# Sheet2.net
KiCad netlist of a schematic drawn in Altium Designer
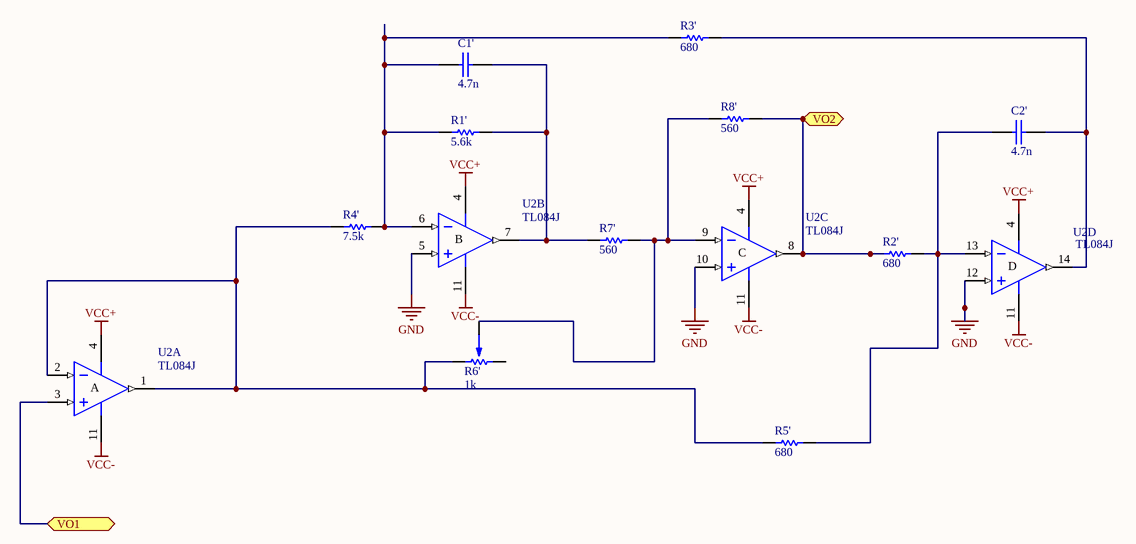
[diagram p0: Sheet2.SchDoc]

(export (version "E")
  (design (tool "Eeschema 10.0.6"))
  (components
    (comp (ref "C1'") (value "4.7n") (footprint "CAP100") (libsource (lib "LIBEBAL") (part "CAP")))
    (comp (ref "C2'") (value "4.7n") (footprint "CAP100") (libsource (lib "LIBEBAL") (part "CAP")))
    (comp (ref "R1'") (value "5.6k") (footprint "0805") (libsource (lib "LIBEBAL") (part "RES")))
    (comp (ref "R2'") (value "680") (footprint "0805") (libsource (lib "LIBEBAL") (part "RES")))
    (comp (ref "R3'") (value "680") (footprint "0805") (libsource (lib "LIBEBAL") (part "RES")))
    (comp (ref "R4'") (value "7.5k") (footprint "0805") (libsource (lib "LIBEBAL") (part "RES")))
    (comp (ref "R5'") (value "680") (footprint "0805") (libsource (lib "LIBEBAL") (part "RES")))
    (comp (ref "R6'") (value "1k") (footprint "PRESET V") (libsource (lib "LIBEBAL") (part "PRESET")))
    (comp (ref "R7'") (value "560") (footprint "0805") (libsource (lib "LIBEBAL") (part "RES")))
    (comp (ref "R8'") (value "560") (footprint "0805") (libsource (lib "LIBEBAL") (part "RES")))
    (comp (ref "U2")
      (value "TL084J")
      (footprint "J014")
      (description "JFET-Input Operational Amplifier")
      (fields (field (name "PUBLISHER") "Altium Limited"))
      (libsource (lib "TI Operational Amplifier") (part "TL084J"))
    )
  )
  (nets
    (net (code "1") (name "/VO1") (class "Default")
      (node (ref "U2") (pin "3") (pinfunction "IN+_3") (pintype "input"))
    )
    (net (code "2") (name "/VO2") (class "Default")
      (node (ref "R2'") (pin "1") (pinfunction "1_1") (pintype "passive"))
      (node (ref "R8'") (pin "2") (pinfunction "2_2") (pintype "passive"))
      (node (ref "U2") (pin "8") (pinfunction "OUT_8") (pintype "output"))
    )
    (net (code "3") (name "GND") (class "Default")
      (node (ref "U2") (pin "10") (pinfunction "IN+_10") (pintype "input"))
      (node (ref "U2") (pin "12") (pinfunction "IN+_12") (pintype "input"))
      (node (ref "U2") (pin "5") (pinfunction "IN+_5") (pintype "input"))
    )
    (net (code "4") (name "Net-(U2A-IN-)") (class "Default")
      (node (ref "R4'") (pin "1") (pinfunction "1_1") (pintype "passive"))
      (node (ref "R5'") (pin "1") (pinfunction "1_1") (pintype "passive"))
      (node (ref "R6'") (pin "1") (pinfunction "1_1") (pintype "passive"))
      (node (ref "U2") (pin "1") (pinfunction "OUT_1") (pintype "output"))
      (node (ref "U2") (pin "2") (pinfunction "IN-_2") (pintype "input"))
    )
    (net (code "5") (name "Net-(U2B-IN-)") (class "Default")
      (node (ref "C1'") (pin "1") (pinfunction "1_1") (pintype "passive"))
      (node (ref "R1'") (pin "1") (pinfunction "1_1") (pintype "passive"))
      (node (ref "R3'") (pin "1") (pinfunction "1_1") (pintype "passive"))
      (node (ref "R4'") (pin "2") (pinfunction "2_2") (pintype "passive"))
      (node (ref "U2") (pin "6") (pinfunction "IN-_6") (pintype "input"))
    )
    (net (code "6") (name "Net-(U2B-OUT)") (class "Default")
      (node (ref "C1'") (pin "2") (pinfunction "2_2") (pintype "passive"))
      (node (ref "R1'") (pin "2") (pinfunction "2_2") (pintype "passive"))
      (node (ref "R7'") (pin "1") (pinfunction "1_1") (pintype "passive"))
      (node (ref "U2") (pin "7") (pinfunction "OUT_7") (pintype "output"))
    )
    (net (code "7") (name "Net-(U2C-IN-)") (class "Default")
      (node (ref "R6'") (pin "2") (pinfunction "2_2") (pintype "passive"))
      (node (ref "R7'") (pin "2") (pinfunction "2_2") (pintype "passive"))
      (node (ref "R8'") (pin "1") (pinfunction "1_1") (pintype "passive"))
      (node (ref "U2") (pin "9") (pinfunction "IN-_9") (pintype "input"))
    )
    (net (code "8") (name "Net-(U2D-IN-)") (class "Default")
      (node (ref "C2'") (pin "1") (pinfunction "1_1") (pintype "passive"))
      (node (ref "R2'") (pin "2") (pinfunction "2_2") (pintype "passive"))
      (node (ref "R5'") (pin "2") (pinfunction "2_2") (pintype "passive"))
      (node (ref "U2") (pin "13") (pinfunction "IN-_13") (pintype "input"))
    )
    (net (code "9") (name "Net-(U2D-OUT)") (class "Default")
      (node (ref "C2'") (pin "2") (pinfunction "2_2") (pintype "passive"))
      (node (ref "R3'") (pin "2") (pinfunction "2_2") (pintype "passive"))
      (node (ref "U2") (pin "14") (pinfunction "OUT_14") (pintype "output"))
    )
    (net (code "10") (name "VCC+") (class "Default")
      (node (ref "U2") (pin "4") (pinfunction "V+_4") (pintype "power_in"))
    )
    (net (code "11") (name "VCC-") (class "Default")
      (node (ref "U2") (pin "11") (pinfunction "V-_11") (pintype "power_in"))
    )
    (net (code "12") (name "unconnected-(R6'-Pad3)") (class "Default")
      (node (ref "R6'") (pin "3") (pinfunction "3_3") (pintype "passive"))
    )
  )
)
